# bolid-iso-protium.net
KiCad netlist of a schematic drawn in Altium Designer
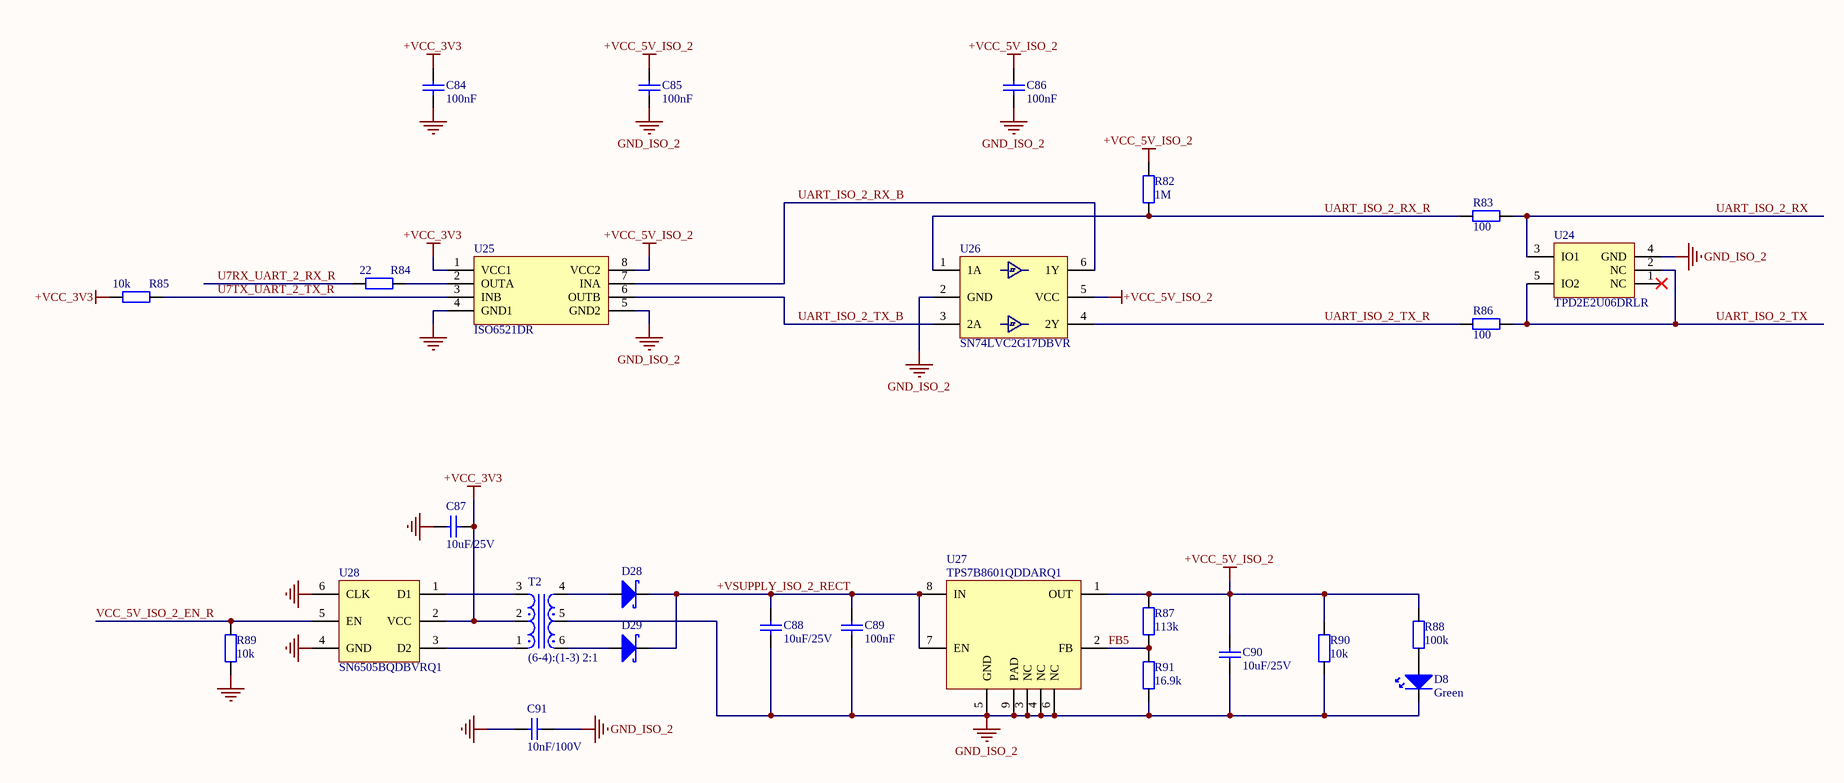
[diagram p0: bolid-iso-protium.SchDoc]

(export (version "E")
  (design (tool "Eeschema 10.0.6"))
  (components
    (comp (ref "C84")
      (value "GRM155R71H104KE14D")
      (footprint "C0402-CAPC100X50X55L22 - Tayio Yuden TDK")
      (description "MLCC 0402 (1005) 100nF 10% 50V X7R")
      (fields
        (field (name "MANUFACTURER") "Murata Electronics")
        (field (name "TOLERANCE") "10 %")
        (field (name "VALUE DISPLAYED") "100nF")
      )
      (libsource (lib "capacitors2") (part "GRM155R71H104KE14D"))
    )
    (comp (ref "C85")
      (value "GRM155R71H104KE14D")
      (footprint "C0402-CAPC100X50X55L22 - Tayio Yuden TDK")
      (description "MLCC 0402 (1005) 100nF 10% 50V X7R")
      (fields
        (field (name "MANUFACTURER") "Murata Electronics")
        (field (name "TOLERANCE") "10 %")
        (field (name "VALUE DISPLAYED") "100nF")
      )
      (libsource (lib "capacitors2") (part "GRM155R71H104KE14D"))
    )
    (comp (ref "C86")
      (value "GRM155R71H104KE14D")
      (footprint "C0402-CAPC100X50X55L22 - Tayio Yuden TDK")
      (description "MLCC 0402 (1005) 100nF 10% 50V X7R")
      (fields
        (field (name "MANUFACTURER") "Murata Electronics")
        (field (name "TOLERANCE") "10 %")
        (field (name "VALUE DISPLAYED") "100nF")
      )
      (libsource (lib "capacitors2") (part "GRM155R71H104KE14D"))
    )
    (comp (ref "C87")
      (value "TMK316AB7106KL-T")
      (footprint "C1206-CAPC320X160X190L65N - Murata")
      (description "MLCC 1206 (3216) 10uF 10% 25V X7R")
      (fields
        (field (name "MANUFACTURER") "Taiyo Yuden")
        (field (name "TOLERANCE") "10 %")
        (field (name "VALUE DISPLAYED") "10uF/25V")
      )
      (libsource (lib "capacitors2") (part "TMK316AB7106KL-T"))
    )
    (comp (ref "C88")
      (value "TMK316AB7106KL-T")
      (footprint "C1206-CAPC320X160X190L65N - Murata")
      (description "MLCC 1206 (3216) 10uF 10% 25V X7R")
      (fields
        (field (name "MANUFACTURER") "Taiyo Yuden")
        (field (name "TOLERANCE") "10 %")
        (field (name "VALUE DISPLAYED") "10uF/25V")
      )
      (libsource (lib "capacitors2") (part "TMK316AB7106KL-T"))
    )
    (comp (ref "C89")
      (value "GRM155R71H104KE14D")
      (footprint "C0402-CAPC100X50X55L22 - Tayio Yuden TDK")
      (description "MLCC 0402 (1005) 100nF 10% 50V X7R")
      (fields
        (field (name "MANUFACTURER") "Murata Electronics")
        (field (name "TOLERANCE") "10 %")
        (field (name "VALUE DISPLAYED") "100nF")
      )
      (libsource (lib "capacitors2") (part "GRM155R71H104KE14D"))
    )
    (comp (ref "C90")
      (value "TMK316AB7106KL-T")
      (footprint "C1206-CAPC320X160X190L65N - Murata")
      (description "MLCC 1206 (3216) 10uF 10% 25V X7R")
      (fields
        (field (name "MANUFACTURER") "Taiyo Yuden")
        (field (name "TOLERANCE") "10 %")
        (field (name "VALUE DISPLAYED") "10uF/25V")
      )
      (libsource (lib "capacitors2") (part "TMK316AB7106KL-T"))
    )
    (comp (ref "C91")
      (value "GRM188R72A103KA01J")
      (footprint "C0603-CAPC162X80X95L35N")
      (description "MLCC 0603 (1608) 10nF 10% 100V X7R")
      (fields
        (field (name "MANUFACTURER") "Murata Electronics")
        (field (name "TOLERANCE") "10 %")
        (field (name "VALUE DISPLAYED") "10nF/100V")
      )
      (libsource (lib "capacitors2") (part "GRM188R72A103KA01J"))
    )
    (comp (ref "D8")
      (value "150060GS75000")
      (footprint "D0603 DIONC166X84X36L42N Littelfuse")
      (description "LED 0603 (1608) Green")
      (fields (field (name "MANUFACTURER") "Wurth Elektronik") (field (name "ILLUMINATION COLOR") "Green"))
      (libsource (lib "semiconductors2") (part "150060GS75000"))
    )
    (comp (ref "D28")
      (value "MBR0530T3G")
      (footprint "SOD-123-2L SOD375X160X128L32X60N - Fairchild")
      (description "ON Semi MBR0530T3G; SMT Schottky Diode; 30V 500mA; 2-Pin SOD-123")
      (fields (field (name "MANUFACTURER") "ON Semiconductor"))
      (libsource (lib "semiconductors2") (part "MBR0530T3G"))
    )
    (comp (ref "D29")
      (value "MBR0530T3G")
      (footprint "SOD-123-2L SOD375X160X128L32X60N - Fairchild")
      (description "ON Semi MBR0530T3G; SMT Schottky Diode; 30V 500mA; 2-Pin SOD-123")
      (fields (field (name "MANUFACTURER") "ON Semiconductor"))
      (libsource (lib "semiconductors2") (part "MBR0530T3G"))
    )
    (comp (ref "R82")
      (value "1M")
      (footprint "R0402-RESC100X50X40L22N")
      (description "RES 0402 (1005) 1.00M 1% 0.0625W 50V Thick Film")
      (fields
        (field (name "MANUFACTURER") "YAGEO")
        (field (name "MANUFACTURER PART NUMBER") "AC0402FR-071ML")
      )
      (libsource (lib "resistors2") (part "AC0402FR-071ML"))
    )
    (comp (ref "R83")
      (value "100")
      (footprint "R0402-RESC100X50X40L22N")
      (description "RES 0402 (1005) 100.0 ohm 1% 0.0625W 50V Thick Film")
      (fields
        (field (name "MANUFACTURER") "Yageo")
        (field (name "MANUFACTURER PART NUMBER") "RC0402FR-07100RL")
      )
      (libsource (lib "resistors2") (part "RC0402FR-07100RL"))
    )
    (comp (ref "R84")
      (value "22")
      (footprint "R0402-RESC100X50X40L22N")
      (description "RES 0402 (1005) 22.0 ohm 1% 0.0625W 50V Thick Film")
      (fields
        (field (name "MANUFACTURER") "Yageo")
        (field (name "MANUFACTURER PART NUMBER") "RC0402FR-1322RL")
      )
      (libsource (lib "resistors2") (part "RC0402FR-1322RL"))
    )
    (comp (ref "R85")
      (value "10k")
      (footprint "R0402-RESC100X50X40L22N")
      (description "RES 0402 (1005) 10.0k 1% 0.0625W 50V Thick Film")
      (fields
        (field (name "MANUFACTURER") "Yageo")
        (field (name "MANUFACTURER PART NUMBER") "RC0402FR-0710KL")
      )
      (libsource (lib "") (part "RC0402FR-0710KL_1"))
    )
    (comp (ref "R86")
      (value "100")
      (footprint "R0402-RESC100X50X40L22N")
      (description "RES 0402 (1005) 100.0 ohm 1% 0.0625W 50V Thick Film")
      (fields
        (field (name "MANUFACTURER") "Yageo")
        (field (name "MANUFACTURER PART NUMBER") "RC0402FR-07100RL")
      )
      (libsource (lib "resistors2") (part "RC0402FR-07100RL"))
    )
    (comp (ref "R87")
      (value "113k")
      (footprint "R0402-RESC100X50X40L22N")
      (description "RES 0402 (1005) 113.0k 1% 0.0625W 50V Thick Film")
      (fields
        (field (name "MANUFACTURER") "Yageo")
        (field (name "MANUFACTURER PART NUMBER") "RC0402FR-07113KL")
      )
      (libsource (lib "resistors2") (part "RC0402FR-07113KL"))
    )
    (comp (ref "R88")
      (value "100k")
      (footprint "R0402-RESC100X50X40L22N")
      (description "RES 0402 (1005) 100.0k 1% 0.0625W 50V Thick Film")
      (fields
        (field (name "MANUFACTURER") "Yageo")
        (field (name "MANUFACTURER PART NUMBER") "RC0402FR-07100KL")
      )
      (libsource (lib "resistors2") (part "RC0402FR-07100KL"))
    )
    (comp (ref "R89")
      (value "10k")
      (footprint "R0402-RESC100X50X40L22N")
      (description "RES 0402 (1005) 10.0k 1% 0.0625W 50V Thick Film")
      (fields
        (field (name "MANUFACTURER") "Yageo")
        (field (name "MANUFACTURER PART NUMBER") "RC0402FR-0710KL")
      )
      (libsource (lib "resistors2") (part "RC0402FR-0710KL"))
    )
    (comp (ref "R90")
      (value "10k")
      (footprint "R0402-RESC100X50X40L22N")
      (description "RES 0402 (1005) 10.0k 1% 0.0625W 50V Thick Film")
      (fields
        (field (name "MANUFACTURER") "Yageo")
        (field (name "MANUFACTURER PART NUMBER") "RC0402FR-0710KL")
      )
      (libsource (lib "resistors2") (part "RC0402FR-0710KL"))
    )
    (comp (ref "R91")
      (value "16.9k")
      (footprint "R0402-RESC100X50X40L22N")
      (description "RES 0402 (1005) 16.9k 1% 0.0625W 50V Thick Film")
      (fields
        (field (name "MANUFACTURER") "Yageo")
        (field (name "MANUFACTURER PART NUMBER") "RC0402FR-0716K9L")
      )
      (libsource (lib "resistors2") (part "RC0402FR-0716K9L"))
    )
    (comp (ref "T2")
      (value "(6-4):(1-3) 2:1")
      (footprint "WE 760390014")
      (description "Transformer 2:1 11VuS 150mAAC Power Transformers MID-SN6501 TI Driver Toroid .475mH 3.3VDC")
      (fields
        (field (name "MANUFACTURER") "Wurth Elektronik / Midcom")
        (field (name "MANUFACTURER PART NUMBER") "760390015")
      )
      (libsource (lib "inductors2") (part "760390015"))
    )
    (comp (ref "U24")
      (value "TPD2E2U06DRLR")
      (footprint "TI SOT-5X3 DRL0005A SOTFL50P160X60-5N")
      (description "TVS DIODE 5.5VWM 12.4VC 5SOT")
      (fields (field (name "MANUFACTURER") "Texas Instruments"))
      (libsource (lib "semiconductors2") (part "TPD2E2U06DRLR"))
    )
    (comp (ref "U25")
      (value "ISO6521DR")
      (footprint "TI SOIC8 D0008A SOIC8P127_490X599X175L84X41N")
      (description "Functional isolation dual-channel 1/1 digital isolator 8-SOIC -40 to 125")
      (fields (field (name "MANUFACTURER") "Texas Instruments"))
      (libsource (lib "ics2") (part "ISO6521DR"))
    )
    (comp (ref "U26")
      (value "SN74LVC2G17DBVR")
      (footprint "TI SOT23 DBV0006A SOT23-6P95_280X145L45X37N")
      (description "2-ch, 1.65-V to 5.5-V buffers with Schmitt-Trigger inputs 6-SOT-23 -40 to 125")
      (fields (field (name "MANUFACTURER") "Texas Instruments"))
      (libsource (lib "ics2") (part "SN74LVC2G17DBVR"))
    )
    (comp (ref "U27")
      (value "TPS7B8601QDDARQ1")
      (footprint "TI SOIC8 DDA0008E-C01 SOIC127P600X170_HS-9N")
      (fields (field (name "MANUFACTURER") "Texas Instruments"))
      (libsource (lib "ics2") (part "TPS7B8601QDDARQ1"))
    )
    (comp (ref "U28")
      (value "SN6505BQDBVRQ1")
      (footprint "TI SOT23 DBV0006A SOT23-6P95_280X145L45X37N")
      (description "Power Management Specialized - PMIC A 595-SN6505BQDBVTQ1")
      (fields (field (name "MANUFACTURER") "Texas Instruments"))
      (libsource (lib "ics2") (part "SN6505BQDBVRQ1"))
    )
  )
  (nets
    (net (code "1") (name "+VCC_3V3") (class "Default")
      (node (ref "C84") (pin "2") (pinfunction "2_2") (pintype "passive"))
      (node (ref "C87") (pin "2") (pinfunction "2_2") (pintype "passive"))
      (node (ref "R85") (pin "2") (pinfunction "2_2") (pintype "passive"))
      (node (ref "T2") (pin "2") (pinfunction "2_2") (pintype "passive"))
      (node (ref "U25") (pin "1") (pinfunction "VCC1_1") (pintype "passive"))
      (node (ref "U28") (pin "2") (pinfunction "VCC_2") (pintype "passive"))
    )
    (net (code "2") (name "+VCC_5V_ISO_2") (class "Default")
      (node (ref "C85") (pin "2") (pinfunction "2_2") (pintype "passive"))
      (node (ref "C86") (pin "2") (pinfunction "2_2") (pintype "passive"))
      (node (ref "C90") (pin "2") (pinfunction "2_2") (pintype "passive"))
      (node (ref "R82") (pin "2") (pinfunction "2_2") (pintype "passive"))
      (node (ref "R87") (pin "2") (pinfunction "2_2") (pintype "passive"))
      (node (ref "R88") (pin "2") (pinfunction "2_2") (pintype "passive"))
      (node (ref "R90") (pin "2") (pinfunction "2_2") (pintype "passive"))
      (node (ref "U25") (pin "8") (pinfunction "VCC2_8") (pintype "passive"))
      (node (ref "U26") (pin "5") (pinfunction "VCC_5") (pintype "passive"))
      (node (ref "U27") (pin "1") (pinfunction "OUT_1") (pintype "passive"))
    )
    (net (code "3") (name "/+VSUPPLY_ISO_2_RECT") (class "Default")
      (node (ref "C88") (pin "2") (pinfunction "2_2") (pintype "passive"))
      (node (ref "C89") (pin "2") (pinfunction "2_2") (pintype "passive"))
      (node (ref "D28") (pin "1") (pinfunction "K_1") (pintype "passive"))
      (node (ref "D29") (pin "1") (pinfunction "K_1") (pintype "passive"))
      (node (ref "U27") (pin "7") (pinfunction "EN_7") (pintype "passive"))
      (node (ref "U27") (pin "8") (pinfunction "IN_8") (pintype "passive"))
    )
    (net (code "4") (name "/FB5") (class "Default")
      (node (ref "R87") (pin "1") (pinfunction "1_1") (pintype "passive"))
      (node (ref "R91") (pin "2") (pinfunction "2_2") (pintype "passive"))
      (node (ref "U27") (pin "2") (pinfunction "FB_2") (pintype "passive"))
    )
    (net (code "5") (name "/U7RX_UART_2_RX_R") (class "Default")
      (node (ref "R84") (pin "1") (pinfunction "1_1") (pintype "passive"))
    )
    (net (code "6") (name "/U7TX_UART_2_TX_R") (class "Default")
      (node (ref "R85") (pin "1") (pinfunction "1_1") (pintype "passive"))
      (node (ref "U25") (pin "3") (pinfunction "INB_3") (pintype "passive"))
    )
    (net (code "7") (name "/UART_ISO_2_RX") (class "Default")
      (node (ref "R83") (pin "2") (pinfunction "2_2") (pintype "passive"))
      (node (ref "U24") (pin "3") (pinfunction "IO1_3") (pintype "passive"))
    )
    (net (code "8") (name "/UART_ISO_2_RX_B") (class "Default")
      (node (ref "U25") (pin "7") (pinfunction "INA_7") (pintype "passive"))
      (node (ref "U26") (pin "6") (pinfunction "1Y_6") (pintype "passive"))
    )
    (net (code "9") (name "/UART_ISO_2_RX_R") (class "Default")
      (node (ref "R82") (pin "1") (pinfunction "1_1") (pintype "passive"))
      (node (ref "R83") (pin "1") (pinfunction "1_1") (pintype "passive"))
      (node (ref "U26") (pin "1") (pinfunction "1A_1") (pintype "passive"))
    )
    (net (code "10") (name "/UART_ISO_2_TX") (class "Default")
      (node (ref "R86") (pin "2") (pinfunction "2_2") (pintype "passive"))
      (node (ref "U24") (pin "2") (pinfunction "NC_2") (pintype "passive"))
      (node (ref "U24") (pin "5") (pinfunction "IO2_5") (pintype "passive"))
    )
    (net (code "11") (name "/UART_ISO_2_TX_B") (class "Default")
      (node (ref "U25") (pin "6") (pinfunction "OUTB_6") (pintype "passive"))
      (node (ref "U26") (pin "3") (pinfunction "2A_3") (pintype "passive"))
    )
    (net (code "12") (name "/UART_ISO_2_TX_R") (class "Default")
      (node (ref "R86") (pin "1") (pinfunction "1_1") (pintype "passive"))
      (node (ref "U26") (pin "4") (pinfunction "2Y_4") (pintype "passive"))
    )
    (net (code "13") (name "/VCC_5V_ISO_2_EN_R") (class "Default")
      (node (ref "R89") (pin "2") (pinfunction "2_2") (pintype "passive"))
      (node (ref "U28") (pin "5") (pinfunction "EN_5") (pintype "passive"))
    )
    (net (code "14") (name "GND") (class "Default")
      (node (ref "C84") (pin "1") (pinfunction "1_1") (pintype "passive"))
      (node (ref "C87") (pin "1") (pinfunction "1_1") (pintype "passive"))
      (node (ref "C91") (pin "1") (pinfunction "1_1") (pintype "passive"))
      (node (ref "R89") (pin "1") (pinfunction "1_1") (pintype "passive"))
      (node (ref "U25") (pin "4") (pinfunction "GND1_4") (pintype "passive"))
      (node (ref "U28") (pin "4") (pinfunction "GND_4") (pintype "passive"))
      (node (ref "U28") (pin "6") (pinfunction "CLK_6") (pintype "passive"))
    )
    (net (code "15") (name "GND_ISO_2") (class "Default")
      (node (ref "C85") (pin "1") (pinfunction "1_1") (pintype "passive"))
      (node (ref "C86") (pin "1") (pinfunction "1_1") (pintype "passive"))
      (node (ref "C88") (pin "1") (pinfunction "1_1") (pintype "passive"))
      (node (ref "C89") (pin "1") (pinfunction "1_1") (pintype "passive"))
      (node (ref "C90") (pin "1") (pinfunction "1_1") (pintype "passive"))
      (node (ref "C91") (pin "2") (pinfunction "2_2") (pintype "passive"))
      (node (ref "D8") (pin "1") (pinfunction "K_1") (pintype "passive"))
      (node (ref "R90") (pin "1") (pinfunction "1_1") (pintype "passive"))
      (node (ref "R91") (pin "1") (pinfunction "1_1") (pintype "passive"))
      (node (ref "T2") (pin "5") (pinfunction "5_5") (pintype "passive"))
      (node (ref "U24") (pin "4") (pinfunction "GND_4") (pintype "passive"))
      (node (ref "U25") (pin "5") (pinfunction "GND2_5") (pintype "passive"))
      (node (ref "U26") (pin "2") (pinfunction "GND_2") (pintype "passive"))
      (node (ref "U27") (pin "3") (pinfunction "NC_3") (pintype "passive"))
      (node (ref "U27") (pin "4") (pinfunction "NC_4") (pintype "passive"))
      (node (ref "U27") (pin "5") (pinfunction "GND_5") (pintype "passive"))
      (node (ref "U27") (pin "6") (pinfunction "NC_6") (pintype "passive"))
      (node (ref "U27") (pin "9") (pinfunction "PAD_9") (pintype "passive"))
    )
    (net (code "16") (name "Net-(D8-A)") (class "Default")
      (node (ref "D8") (pin "2") (pinfunction "A_2") (pintype "passive"))
      (node (ref "R88") (pin "1") (pinfunction "1_1") (pintype "passive"))
    )
    (net (code "17") (name "Net-(D28-A)") (class "Default")
      (node (ref "D28") (pin "2") (pinfunction "A_2") (pintype "passive"))
      (node (ref "T2") (pin "4") (pinfunction "4_4") (pintype "passive"))
    )
    (net (code "18") (name "Net-(D29-A)") (class "Default")
      (node (ref "D29") (pin "2") (pinfunction "A_2") (pintype "passive"))
      (node (ref "T2") (pin "6") (pinfunction "6_6") (pintype "passive"))
    )
    (net (code "19") (name "Net-(U25-OUTA)") (class "Default")
      (node (ref "R84") (pin "2") (pinfunction "2_2") (pintype "passive"))
      (node (ref "U25") (pin "2") (pinfunction "OUTA_2") (pintype "passive"))
    )
    (net (code "20") (name "Net-(U28-D1)") (class "Default")
      (node (ref "T2") (pin "3") (pinfunction "3_3") (pintype "passive"))
      (node (ref "U28") (pin "1") (pinfunction "D1_1") (pintype "passive"))
    )
    (net (code "21") (name "Net-(U28-D2)") (class "Default")
      (node (ref "T2") (pin "1") (pinfunction "1_1") (pintype "passive"))
      (node (ref "U28") (pin "3") (pinfunction "D2_3") (pintype "passive"))
    )
    (net (code "22") (name "unconnected-(U24-NC-Pad1)") (class "Default")
      (node (ref "U24") (pin "1") (pinfunction "NC_1") (pintype "passive+no_connect"))
    )
  )
)
